# photon.net
KiCad netlist of a schematic drawn in EAGLE
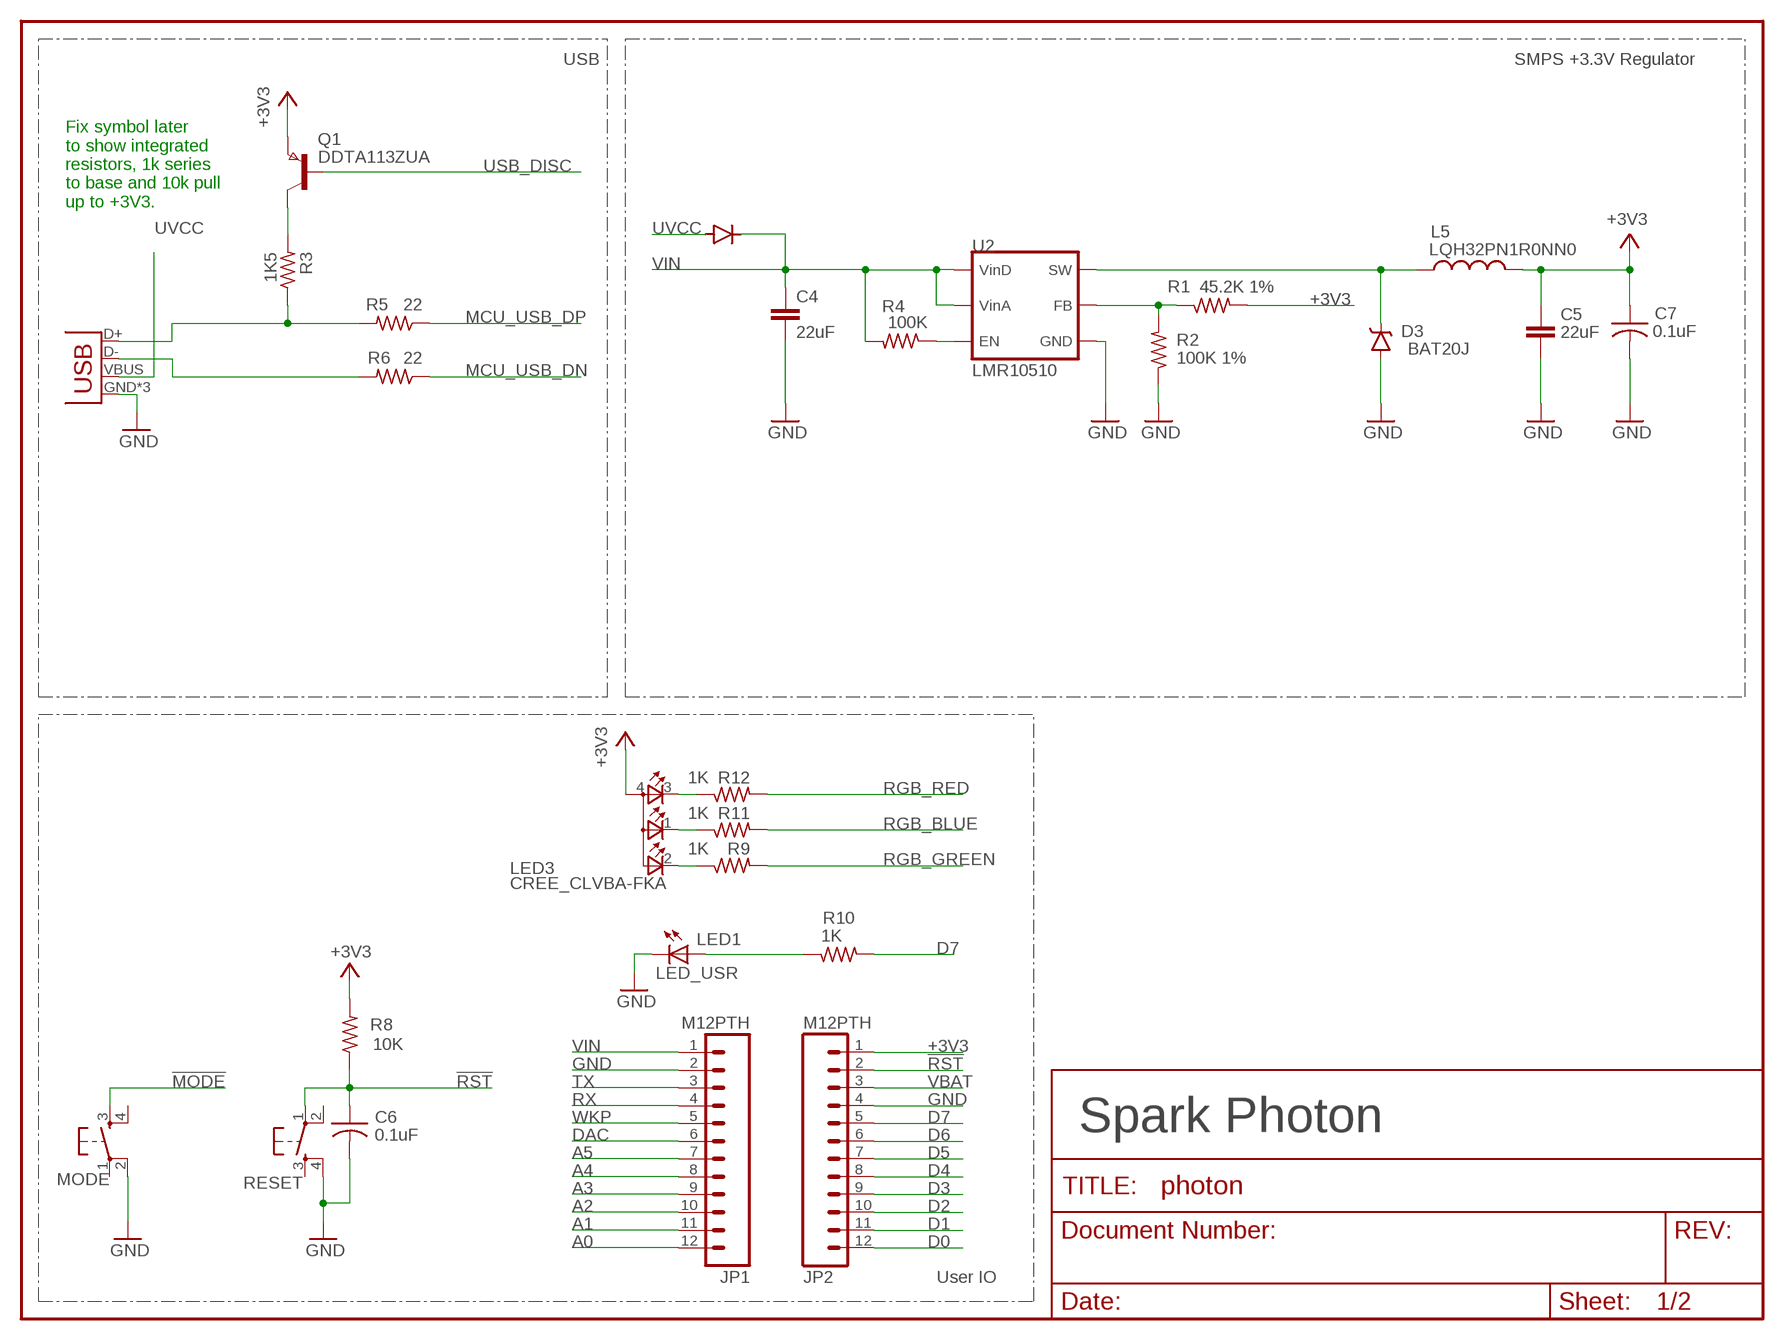
[diagram p0: schematic, sheet 1]
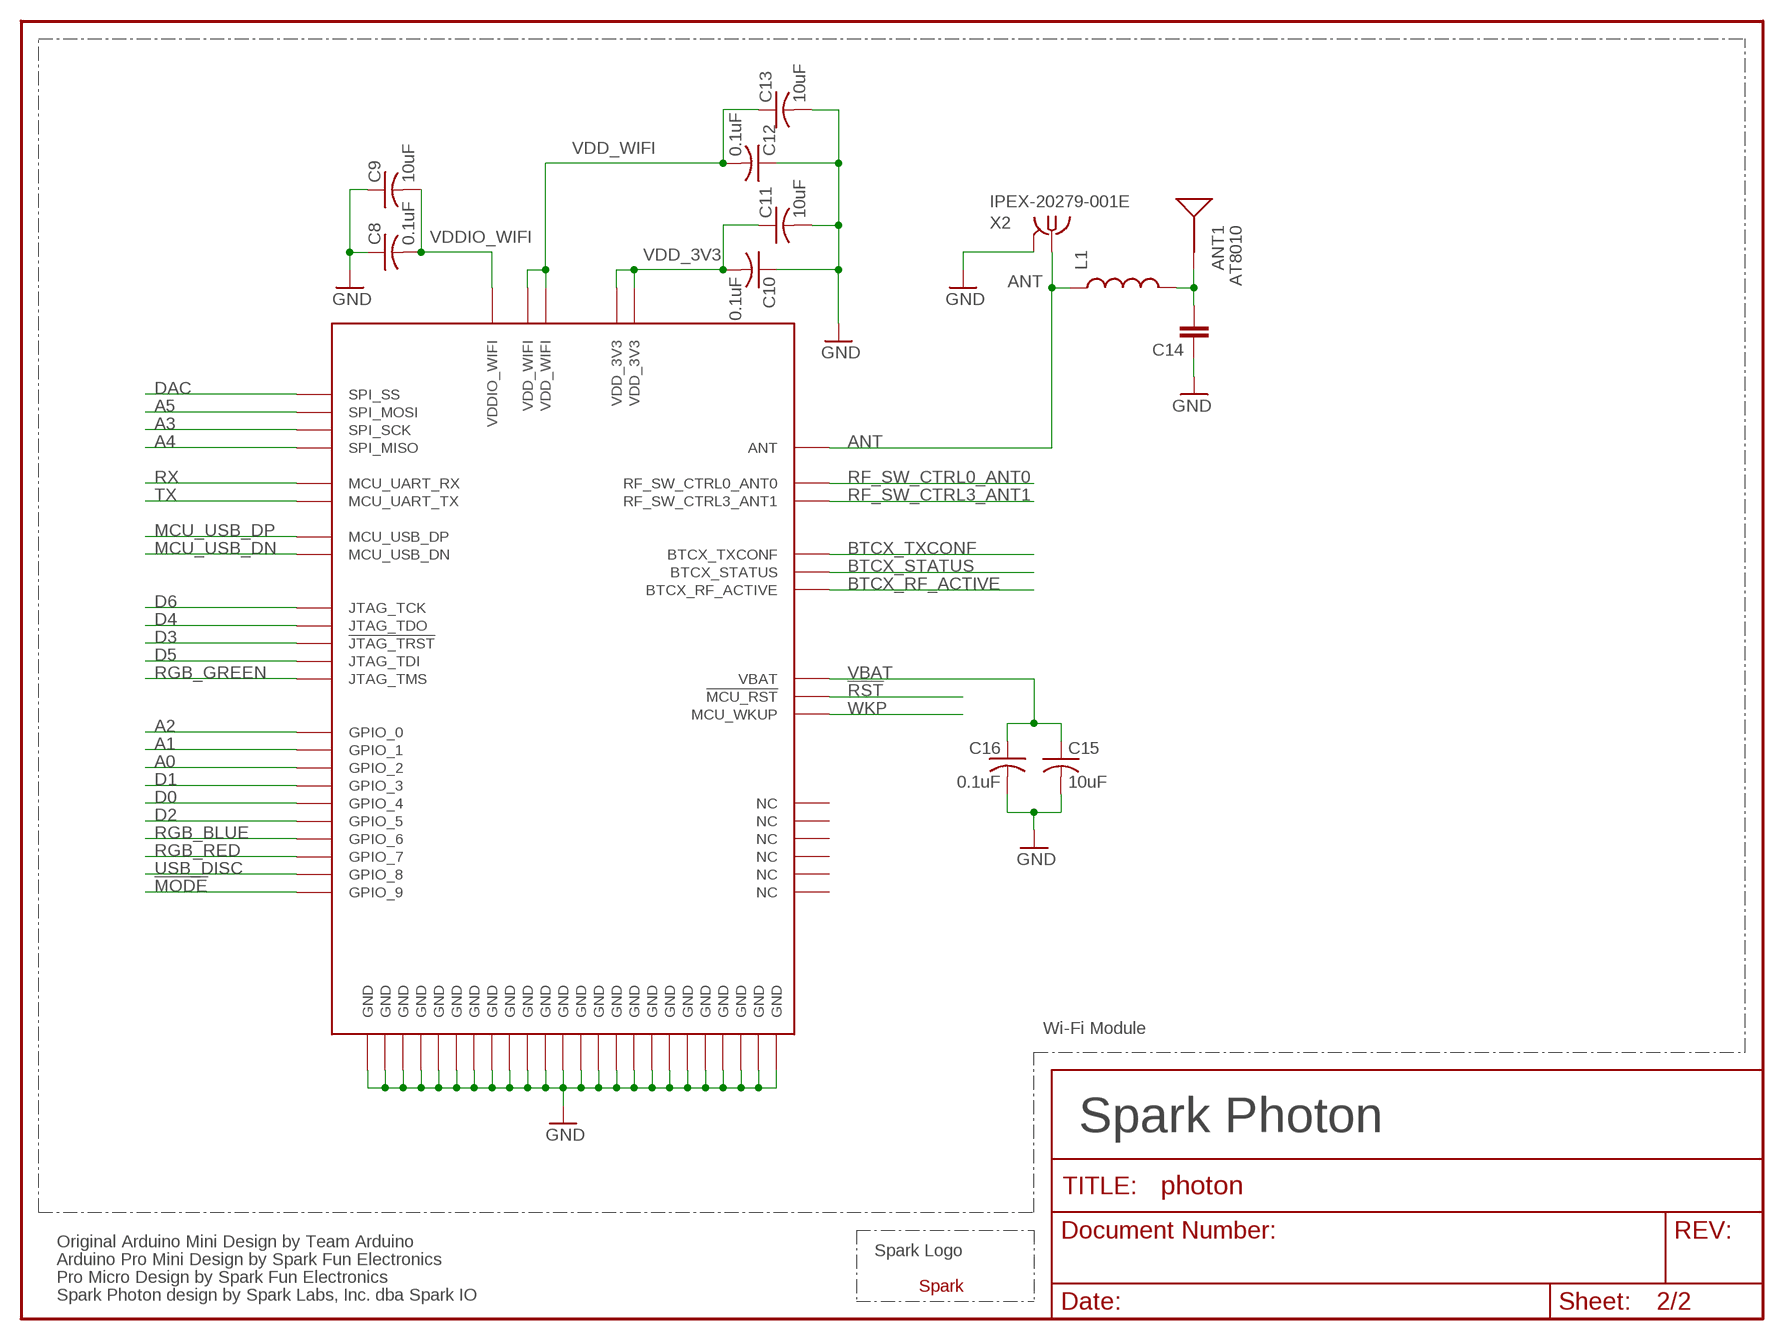
[diagram p1: schematic, sheet 2]

(export (version "E")
  (design (tool "Eeschema 10.0.6"))
  (components
    (comp (ref "ANT1")
      (value "AT8010")
      (footprint "eagle-import:AT8010")
      (libsource (lib "eagle-import") (part "AT8010"))
    )
    (comp (ref "C8")
      (value "0.1uF")
      (footprint "eagle-import:C0402")
      (libsource (lib "eagle-import") (part "C-USC0402"))
    )
    (comp (ref "C9")
      (value "10uF")
      (footprint "eagle-import:C0402")
      (libsource (lib "eagle-import") (part "C-USC0402"))
    )
    (comp (ref "C10")
      (value "0.1uF")
      (footprint "eagle-import:C0402")
      (libsource (lib "eagle-import") (part "C-USC0402"))
    )
    (comp (ref "C11")
      (value "10uF")
      (footprint "eagle-import:C0402")
      (libsource (lib "eagle-import") (part "C-USC0402"))
    )
    (comp (ref "C12")
      (value "0.1uF")
      (footprint "eagle-import:C0402")
      (libsource (lib "eagle-import") (part "C-USC0402"))
    )
    (comp (ref "C13")
      (value "10uF")
      (footprint "eagle-import:C0402")
      (libsource (lib "eagle-import") (part "C-USC0402"))
    )
    (comp (ref "C14")
      (value "CAP0603-CAP")
      (footprint "eagle-import:0603-CAP")
      (libsource (lib "eagle-import") (part "CAP0603-CAP"))
    )
    (comp (ref "C15")
      (value "10uF")
      (footprint "eagle-import:C0402")
      (libsource (lib "eagle-import") (part "C-USC0402"))
    )
    (comp (ref "C16")
      (value "0.1uF")
      (footprint "eagle-import:C0402")
      (libsource (lib "eagle-import") (part "C-USC0402"))
    )
    (comp (ref "L1")
      (value "INDUCTOR-SPARKFUN0603")
      (footprint "eagle-import:0603")
      (libsource (lib "eagle-import") (part "INDUCTOR-SPARKFUN0603"))
    )
    (comp (ref "U$2")
      (value "SPARK_LOGO2")
      (footprint "eagle-import:SPARK_LOGO2")
      (libsource (lib "eagle-import") (part "SPARK_LOGO2"))
    )
    (comp (ref "U1")
      (value "WM-N-BM-09")
      (footprint "eagle-import:WM-N-BM-09")
      (libsource (lib "eagle-import") (part "WM-N-BM-09"))
    )
    (comp (ref "X2")
      (value "IPEX-20279-001E")
      (footprint "eagle-import:IPEX-20279-001E")
      (libsource (lib "eagle-import") (part "IPEX-20279-001E"))
    )
    (comp (ref "C4")
      (value "22uF")
      (footprint "eagle-import:C0603")
      (libsource (lib "eagle-import") (part "C-EUC0603"))
    )
    (comp (ref "C5")
      (value "22uF")
      (footprint "eagle-import:C0603")
      (libsource (lib "eagle-import") (part "C-EUC0603"))
    )
    (comp (ref "C6")
      (value "0.1uF")
      (footprint "eagle-import:C0402")
      (libsource (lib "eagle-import") (part "C-USC0402"))
    )
    (comp (ref "C7")
      (value "0.1uF")
      (footprint "eagle-import:C0402")
      (libsource (lib "eagle-import") (part "C-USC0402"))
    )
    (comp (ref "D1")
      (value "DIODE")
      (footprint "eagle-import:DIODE-DO-220AA(SMP)")
      (libsource (lib "eagle-import") (part "DIODE"))
    )
    (comp (ref "D3")
      (value "BAT20J")
      (footprint "eagle-import:SOD-323")
      (libsource (lib "eagle-import") (part "DIODE-SCHOTTKY-BAT20J"))
    )
    (comp (ref "JP1")
      (value "M12PTH")
      (footprint "eagle-import:1X12-SMALL-PADS")
      (libsource (lib "eagle-import") (part "M12PTH"))
    )
    (comp (ref "JP2")
      (value "M12PTH")
      (footprint "eagle-import:1X12-SMALL-PADS")
      (libsource (lib "eagle-import") (part "M12PTH"))
    )
    (comp (ref "L5")
      (value "LQH32PN1R0NN0")
      (footprint "eagle-import:1210")
      (libsource (lib "eagle-import") (part "INDUCTOR-SPARKFUN1210"))
    )
    (comp (ref "LED3")
      (value "CREE_CLVBA-FKA")
      (footprint "eagle-import:P-LCC-4-3")
      (libsource (lib "eagle-import") (part "TOPLED-3CREE_CLVBA-FKA"))
    )
    (comp (ref "LED_USR")
      (value "LED0603")
      (footprint "eagle-import:LED-0603")
      (libsource (lib "eagle-import") (part "LED0603"))
    )
    (comp (ref "MODE")
      (value "KMR211GLFS")
      (footprint "eagle-import:TACTILE_SWITCH_SMD")
      (libsource (lib "eagle-import") (part "TAC_SWITCHSMD"))
    )
    (comp (ref "Q1")
      (value "DDTA113ZUA")
      (footprint "eagle-import:SOT323")
      (fields (field (name "MPN") "2DB1689-7"))
      (libsource (lib "eagle-import") (part "PNPSOT323"))
    )
    (comp (ref "R1")
      (value "45.2K 1%")
      (footprint "eagle-import:R0402")
      (libsource (lib "eagle-import") (part "R-US_R0402"))
    )
    (comp (ref "R2")
      (value "100K 1%")
      (footprint "eagle-import:R0402")
      (libsource (lib "eagle-import") (part "R-US_R0402"))
    )
    (comp (ref "R3")
      (value "1K5")
      (footprint "eagle-import:R0402")
      (libsource (lib "eagle-import") (part "rcl_R-US_R0402"))
    )
    (comp (ref "R4")
      (value "100K")
      (footprint "eagle-import:R0402")
      (libsource (lib "eagle-import") (part "R-US_R0402"))
    )
    (comp (ref "R5")
      (value "22")
      (footprint "eagle-import:R0402")
      (libsource (lib "eagle-import") (part "rcl_R-US_R0402"))
    )
    (comp (ref "R6")
      (value "22")
      (footprint "eagle-import:R0402")
      (libsource (lib "eagle-import") (part "rcl_R-US_R0402"))
    )
    (comp (ref "R8")
      (value "10K")
      (footprint "eagle-import:R0402")
      (libsource (lib "eagle-import") (part "R-US_R0402"))
    )
    (comp (ref "R9")
      (value "1K")
      (footprint "eagle-import:R0402")
      (libsource (lib "eagle-import") (part "R-US_R0402"))
    )
    (comp (ref "R10")
      (value "1K")
      (footprint "eagle-import:R0402")
      (libsource (lib "eagle-import") (part "R-US_R0402"))
    )
    (comp (ref "R11")
      (value "1K")
      (footprint "eagle-import:R0402")
      (libsource (lib "eagle-import") (part "R-US_R0402"))
    )
    (comp (ref "R12")
      (value "1K")
      (footprint "eagle-import:R0402")
      (libsource (lib "eagle-import") (part "R-US_R0402"))
    )
    (comp (ref "RESET")
      (value "KMR211GLFS")
      (footprint "eagle-import:TACTILE_SWITCH_SMD")
      (libsource (lib "eagle-import") (part "TAC_SWITCHSMD"))
    )
    (comp (ref "U2")
      (value "LMR10510")
      (footprint "eagle-import:WSON-6-PAD")
      (libsource (lib "eagle-import") (part "LMR10510"))
    )
    (comp (ref "X1")
      (value "USB-MICROB")
      (footprint "eagle-import:USB-MICROB-SLOT-HOLE")
      (libsource (lib "eagle-import") (part "USBUSB-MICROB-SLOT-HOLE"))
    )
  )
  (nets
    (net (code "1") (name "+3V3") (class "Default")
      (node (ref "C5") (pin "1") (pinfunction "1_1") (pintype "passive"))
      (node (ref "C7") (pin "1") (pinfunction "1_1") (pintype "passive"))
      (node (ref "JP2") (pin "1") (pinfunction "1_1") (pintype "passive"))
      (node (ref "L5") (pin "2") (pinfunction "2_2") (pintype "passive"))
      (node (ref "LED3") (pin "4") (pinfunction "A2_4") (pintype "passive"))
      (node (ref "Q1") (pin "3") (pinfunction "E_3") (pintype "passive"))
      (node (ref "R1") (pin "2") (pinfunction "2_2") (pintype "passive"))
      (node (ref "R8") (pin "2") (pinfunction "2_2") (pintype "passive"))
    )
    (net (code "2") (name "A0") (class "Default")
      (node (ref "JP1") (pin "12") (pinfunction "12_12") (pintype "passive"))
      (node (ref "U1") (pin "P$6") (pinfunction "GPIO_2_P$6") (pintype "bidirectional"))
    )
    (net (code "3") (name "A1") (class "Default")
      (node (ref "JP1") (pin "11") (pinfunction "11_11") (pintype "passive"))
      (node (ref "U1") (pin "P$7") (pinfunction "GPIO_1_P$7") (pintype "bidirectional"))
    )
    (net (code "4") (name "A2") (class "Default")
      (node (ref "JP1") (pin "10") (pinfunction "10_10") (pintype "passive"))
      (node (ref "U1") (pin "P$8") (pinfunction "GPIO_0_P$8") (pintype "bidirectional"))
    )
    (net (code "5") (name "A3") (class "Default")
      (node (ref "JP1") (pin "9") (pinfunction "9_9") (pintype "passive"))
      (node (ref "U1") (pin "P$24") (pinfunction "SPI_SCK_P$24") (pintype "bidirectional"))
    )
    (net (code "6") (name "A4") (class "Default")
      (node (ref "JP1") (pin "8") (pinfunction "8_8") (pintype "passive"))
      (node (ref "U1") (pin "P$25") (pinfunction "SPI_MISO_P$25") (pintype "bidirectional"))
    )
    (net (code "7") (name "A5") (class "Default")
      (node (ref "JP1") (pin "7") (pinfunction "7_7") (pintype "passive"))
      (node (ref "U1") (pin "P$23") (pinfunction "SPI_MOSI_P$23") (pintype "bidirectional"))
    )
    (net (code "8") (name "ANT") (class "Default")
      (node (ref "L1") (pin "1") (pinfunction "1_1") (pintype "passive"))
      (node (ref "U1") (pin "P$15") (pinfunction "ANT_P$15") (pintype "bidirectional"))
      (node (ref "X2") (pin "1") (pinfunction "1_1") (pintype "passive"))
    )
    (net (code "9") (name "BTCX_RF_ACTIVE") (class "Default")
      (node (ref "U1") (pin "P$9") (pinfunction "BTCX_RF_ACTIVE_P$9") (pintype "bidirectional"))
    )
    (net (code "10") (name "BTCX_STATUS") (class "Default")
      (node (ref "U1") (pin "P$10") (pinfunction "BTCX_STATUS_P$10") (pintype "bidirectional"))
    )
    (net (code "11") (name "BTCX_TXCONF") (class "Default")
      (node (ref "U1") (pin "P$11") (pinfunction "BTCX_TXCONF_P$11") (pintype "bidirectional"))
    )
    (net (code "12") (name "D0") (class "Default")
      (node (ref "JP2") (pin "12") (pinfunction "12_12") (pintype "passive"))
      (node (ref "U1") (pin "P$4") (pinfunction "GPIO_4_P$4") (pintype "bidirectional"))
    )
    (net (code "13") (name "D1") (class "Default")
      (node (ref "JP2") (pin "11") (pinfunction "11_11") (pintype "passive"))
      (node (ref "U1") (pin "P$5") (pinfunction "GPIO_3_P$5") (pintype "bidirectional"))
    )
    (net (code "14") (name "D2") (class "Default")
      (node (ref "JP2") (pin "10") (pinfunction "10_10") (pintype "passive"))
      (node (ref "U1") (pin "P$3") (pinfunction "GPIO_5_P$3") (pintype "bidirectional"))
    )
    (net (code "15") (name "D3") (class "Default")
      (node (ref "JP2") (pin "9") (pinfunction "9_9") (pintype "passive"))
      (node (ref "U1") (pin "P$42") (pinfunction "~{JTAG_TRST}_P$42") (pintype "bidirectional"))
    )
    (net (code "16") (name "D4") (class "Default")
      (node (ref "JP2") (pin "8") (pinfunction "8_8") (pintype "passive"))
      (node (ref "U1") (pin "P$41") (pinfunction "JTAG_TDO_P$41") (pintype "bidirectional"))
    )
    (net (code "17") (name "D5") (class "Default")
      (node (ref "JP2") (pin "7") (pinfunction "7_7") (pintype "passive"))
      (node (ref "U1") (pin "P$43") (pinfunction "JTAG_TDI_P$43") (pintype "bidirectional"))
    )
    (net (code "18") (name "D6") (class "Default")
      (node (ref "JP2") (pin "6") (pinfunction "6_6") (pintype "passive"))
      (node (ref "U1") (pin "P$40") (pinfunction "JTAG_TCK_P$40") (pintype "bidirectional"))
    )
    (net (code "19") (name "D7") (class "Default")
      (node (ref "JP2") (pin "5") (pinfunction "5_5") (pintype "passive"))
      (node (ref "R10") (pin "2") (pinfunction "2_2") (pintype "passive"))
    )
    (net (code "20") (name "DAC") (class "Default")
      (node (ref "JP1") (pin "6") (pinfunction "6_6") (pintype "passive"))
      (node (ref "U1") (pin "P$22") (pinfunction "SPI_SS_P$22") (pintype "bidirectional"))
    )
    (net (code "21") (name "GND") (class "Default")
      (node (ref "C10") (pin "1") (pinfunction "1_1") (pintype "passive"))
      (node (ref "C11") (pin "2") (pinfunction "2_2") (pintype "passive"))
      (node (ref "C12") (pin "1") (pinfunction "1_1") (pintype "passive"))
      (node (ref "C13") (pin "2") (pinfunction "2_2") (pintype "passive"))
      (node (ref "C14") (pin "1") (pinfunction "1_1") (pintype "passive"))
      (node (ref "C15") (pin "2") (pinfunction "2_2") (pintype "passive"))
      (node (ref "C16") (pin "2") (pinfunction "2_2") (pintype "passive"))
      (node (ref "C4") (pin "2") (pinfunction "2_2") (pintype "passive"))
      (node (ref "C5") (pin "2") (pinfunction "2_2") (pintype "passive"))
      (node (ref "C6") (pin "2") (pinfunction "2_2") (pintype "passive"))
      (node (ref "C7") (pin "2") (pinfunction "2_2") (pintype "passive"))
      (node (ref "C8") (pin "1") (pinfunction "1_1") (pintype "passive"))
      (node (ref "C9") (pin "1") (pinfunction "1_1") (pintype "passive"))
      (node (ref "D3") (pin "A") (pinfunction "A_A") (pintype "passive"))
      (node (ref "JP1") (pin "2") (pinfunction "2_2") (pintype "passive"))
      (node (ref "JP2") (pin "4") (pinfunction "4_4") (pintype "passive"))
      (node (ref "LED_USR") (pin "C") (pinfunction "C_C") (pintype "passive"))
      (node (ref "MODE") (pin "2") (pinfunction "2_2") (pintype "passive"))
      (node (ref "R2") (pin "1") (pinfunction "1_1") (pintype "passive"))
      (node (ref "RESET") (pin "4") (pinfunction "4_4") (pintype "passive"))
      (node (ref "U1") (pin "P$14") (pinfunction "GND_P$14") (pintype "bidirectional"))
      (node (ref "U1") (pin "P$16") (pinfunction "GND_P$16") (pintype "bidirectional"))
      (node (ref "U1") (pin "P$17") (pinfunction "GND_P$17") (pintype "bidirectional"))
      (node (ref "U1") (pin "P$18") (pinfunction "GND_P$18") (pintype "bidirectional"))
      (node (ref "U1") (pin "P$21") (pinfunction "GND_P$21") (pintype "bidirectional"))
      (node (ref "U1") (pin "P$29") (pinfunction "GND_P$29") (pintype "bidirectional"))
      (node (ref "U1") (pin "P$30") (pinfunction "GND_P$30") (pintype "bidirectional"))
      (node (ref "U1") (pin "P$37") (pinfunction "GND_P$37") (pintype "bidirectional"))
      (node (ref "U1") (pin "P$45") (pinfunction "GND_P$45") (pintype "bidirectional"))
      (node (ref "U1") (pin "P$48") (pinfunction "GND_P$48") (pintype "bidirectional"))
      (node (ref "U1") (pin "P$50") (pinfunction "GND_P$50") (pintype "bidirectional"))
      (node (ref "U1") (pin "P$55") (pinfunction "GND_P$55") (pintype "bidirectional"))
      (node (ref "U1") (pin "P$56") (pinfunction "GND_P$56") (pintype "bidirectional"))
      (node (ref "U1") (pin "P$57") (pinfunction "GND_P$57") (pintype "bidirectional"))
      (node (ref "U1") (pin "P$58") (pinfunction "GND_P$58") (pintype "bidirectional"))
      (node (ref "U1") (pin "P$59") (pinfunction "GND_P$59") (pintype "bidirectional"))
      (node (ref "U1") (pin "P$60") (pinfunction "GND_P$60") (pintype "bidirectional"))
      (node (ref "U1") (pin "P$61") (pinfunction "GND_P$61") (pintype "bidirectional"))
      (node (ref "U1") (pin "P$62") (pinfunction "GND_P$62") (pintype "bidirectional"))
      (node (ref "U1") (pin "P$63") (pinfunction "GND_P$63") (pintype "bidirectional"))
      (node (ref "U1") (pin "P$64") (pinfunction "GND_P$64") (pintype "bidirectional"))
      (node (ref "U1") (pin "P$65") (pinfunction "GND_P$65") (pintype "bidirectional"))
      (node (ref "U1") (pin "P$66") (pinfunction "GND_P$66") (pintype "bidirectional"))
      (node (ref "U1") (pin "P$67") (pinfunction "GND_P$67") (pintype "bidirectional"))
      (node (ref "U2") (pin "2") (pinfunction "GND_2") (pintype "power_in"))
      (node (ref "U2") (pin "PAD") (pinfunction "GND_PAD") (pintype "power_in"))
      (node (ref "X1") (pin "GND") (pinfunction "GND_GND") (pintype "bidirectional"))
      (node (ref "X1") (pin "MT1") (pinfunction "GND_MT1") (pintype "bidirectional"))
      (node (ref "X1") (pin "MT2") (pinfunction "GND_MT2") (pintype "bidirectional"))
      (node (ref "X2") (pin "2@1") (pinfunction "GND_2@1") (pintype "passive"))
      (node (ref "X2") (pin "2@2") (pinfunction "GND_2@2") (pintype "passive"))
    )
    (net (code "22") (name "LED1") (class "Default")
      (node (ref "LED_USR") (pin "A") (pinfunction "A_A") (pintype "passive"))
      (node (ref "R10") (pin "1") (pinfunction "1_1") (pintype "passive"))
    )
    (net (code "23") (name "MCU_USB_DN") (class "Default")
      (node (ref "R6") (pin "1") (pinfunction "1_1") (pintype "passive"))
      (node (ref "U1") (pin "P$52") (pinfunction "MCU_USB_DN_P$52") (pintype "bidirectional"))
    )
    (net (code "24") (name "MCU_USB_DP") (class "Default")
      (node (ref "R5") (pin "1") (pinfunction "1_1") (pintype "passive"))
      (node (ref "U1") (pin "P$51") (pinfunction "MCU_USB_DP_P$51") (pintype "bidirectional"))
    )
    (net (code "25") (name "Net-(ANT1-SIGNAL)") (class "Default")
      (node (ref "ANT1") (pin "SIG") (pinfunction "SIGNAL_SIG") (pintype "bidirectional"))
      (node (ref "C14") (pin "2") (pinfunction "2_2") (pintype "passive"))
      (node (ref "L1") (pin "2") (pinfunction "2_2") (pintype "passive"))
    )
    (net (code "26") (name "Net-(LED3-CBLUE)") (class "Default")
      (node (ref "LED3") (pin "1") (pinfunction "CBLUE_1") (pintype "passive"))
      (node (ref "R11") (pin "1") (pinfunction "1_1") (pintype "passive"))
    )
    (net (code "27") (name "Net-(LED3-CGREEN)") (class "Default")
      (node (ref "LED3") (pin "2") (pinfunction "CGREEN_2") (pintype "passive"))
      (node (ref "R9") (pin "1") (pinfunction "1_1") (pintype "passive"))
    )
    (net (code "28") (name "Net-(LED3-CRED)") (class "Default")
      (node (ref "LED3") (pin "3") (pinfunction "CRED_3") (pintype "passive"))
      (node (ref "R12") (pin "1") (pinfunction "1_1") (pintype "passive"))
    )
    (net (code "29") (name "Net-(Q1-C)") (class "Default")
      (node (ref "Q1") (pin "1") (pinfunction "C_1") (pintype "passive"))
      (node (ref "R3") (pin "2") (pinfunction "2_2") (pintype "passive"))
    )
    (net (code "30") (name "Net-(R3-Pad1)") (class "Default")
      (node (ref "R3") (pin "1") (pinfunction "1_1") (pintype "passive"))
      (node (ref "R5") (pin "2") (pinfunction "2_2") (pintype "passive"))
      (node (ref "X1") (pin "D+") (pinfunction "D+_D+") (pintype "bidirectional"))
    )
    (net (code "31") (name "Net-(R6-Pad2)") (class "Default")
      (node (ref "R6") (pin "2") (pinfunction "2_2") (pintype "passive"))
      (node (ref "X1") (pin "D-") (pinfunction "D-_D-") (pintype "bidirectional"))
    )
    (net (code "32") (name "Net-(U2-EN)") (class "Default")
      (node (ref "R4") (pin "1") (pinfunction "1_1") (pintype "passive"))
      (node (ref "U2") (pin "6") (pinfunction "EN_6") (pintype "input"))
    )
    (net (code "33") (name "Net-(U2-FB)") (class "Default")
      (node (ref "R1") (pin "1") (pinfunction "1_1") (pintype "passive"))
      (node (ref "R2") (pin "2") (pinfunction "2_2") (pintype "passive"))
      (node (ref "U2") (pin "1") (pinfunction "FB_1") (pintype "input"))
    )
    (net (code "34") (name "Net-(U2-SW)") (class "Default")
      (node (ref "D3") (pin "C") (pinfunction "C_C") (pintype "passive"))
      (node (ref "L5") (pin "1") (pinfunction "1_1") (pintype "passive"))
      (node (ref "U2") (pin "3") (pinfunction "SW_3") (pintype "output"))
    )
    (net (code "35") (name "RF_SW_CTRL0_ANT0") (class "Default")
      (node (ref "U1") (pin "P$13") (pinfunction "RF_SW_CTRL0_ANT0_P$13") (pintype "bidirectional"))
    )
    (net (code "36") (name "RF_SW_CTRL3_ANT1") (class "Default")
      (node (ref "U1") (pin "P$12") (pinfunction "RF_SW_CTRL3_ANT1_P$12") (pintype "bidirectional"))
    )
    (net (code "37") (name "RGB_BLUE") (class "Default")
      (node (ref "R11") (pin "2") (pinfunction "2_2") (pintype "passive"))
      (node (ref "U1") (pin "P$2") (pinfunction "GPIO_6_P$2") (pintype "bidirectional"))
    )
    (net (code "38") (name "RGB_GREEN") (class "Default")
      (node (ref "R9") (pin "2") (pinfunction "2_2") (pintype "passive"))
      (node (ref "U1") (pin "P$44") (pinfunction "JTAG_TMS_P$44") (pintype "bidirectional"))
    )
    (net (code "39") (name "RGB_RED") (class "Default")
      (node (ref "R12") (pin "2") (pinfunction "2_2") (pintype "passive"))
      (node (ref "U1") (pin "P$1") (pinfunction "GPIO_7_P$1") (pintype "bidirectional"))
    )
    (net (code "40") (name "RX") (class "Default")
      (node (ref "JP1") (pin "4") (pinfunction "4_4") (pintype "passive"))
      (node (ref "U1") (pin "P$38") (pinfunction "MCU_UART_RX_P$38") (pintype "bidirectional"))
    )
    (net (code "41") (name "TX") (class "Default")
      (node (ref "JP1") (pin "3") (pinfunction "3_3") (pintype "passive"))
      (node (ref "U1") (pin "P$39") (pinfunction "MCU_UART_TX_P$39") (pintype "bidirectional"))
    )
    (net (code "42") (name "USB_DISC") (class "Default")
      (node (ref "Q1") (pin "2") (pinfunction "B_2") (pintype "passive"))
      (node (ref "U1") (pin "P$54") (pinfunction "GPIO_8_P$54") (pintype "bidirectional"))
    )
    (net (code "43") (name "UVCC") (class "Default")
      (node (ref "D1") (pin "ANODE") (pinfunction "ANODE_ANODE") (pintype "bidirectional"))
      (node (ref "X1") (pin "VBUS") (pinfunction "VBUS_VBUS") (pintype "bidirectional"))
    )
    (net (code "44") (name "VBAT") (class "Default")
      (node (ref "C15") (pin "1") (pinfunction "1_1") (pintype "passive"))
      (node (ref "C16") (pin "1") (pinfunction "1_1") (pintype "passive"))
      (node (ref "JP2") (pin "3") (pinfunction "3_3") (pintype "passive"))
      (node (ref "U1") (pin "P$28") (pinfunction "VBAT_P$28") (pintype "bidirectional"))
    )
    (net (code "45") (name "VDDIO_WIFI") (class "Default")
      (node (ref "C8") (pin "2") (pinfunction "2_2") (pintype "passive"))
      (node (ref "C9") (pin "2") (pinfunction "2_2") (pintype "passive"))
      (node (ref "U1") (pin "P$49") (pinfunction "VDDIO_WIFI_P$49") (pintype "bidirectional"))
    )
    (net (code "46") (name "VDD_3V3") (class "Default")
      (node (ref "C10") (pin "2") (pinfunction "2_2") (pintype "passive"))
      (node (ref "C11") (pin "1") (pinfunction "1_1") (pintype "passive"))
      (node (ref "U1") (pin "P$46") (pinfunction "VDD_3V3_P$46") (pintype "bidirectional"))
      (node (ref "U1") (pin "P$47") (pinfunction "VDD_3V3_P$47") (pintype "bidirectional"))
    )
    (net (code "47") (name "VDD_WIFI") (class "Default")
      (node (ref "C12") (pin "2") (pinfunction "2_2") (pintype "passive"))
      (node (ref "C13") (pin "1") (pinfunction "1_1") (pintype "passive"))
      (node (ref "U1") (pin "P$19") (pinfunction "VDD_WIFI_P$19") (pintype "bidirectional"))
      (node (ref "U1") (pin "P$20") (pinfunction "VDD_WIFI_P$20") (pintype "bidirectional"))
    )
    (net (code "48") (name "VIN") (class "Default")
      (node (ref "C4") (pin "1") (pinfunction "1_1") (pintype "passive"))
      (node (ref "D1") (pin "CATHODE") (pinfunction "CATHODE_CATHODE") (pintype "bidirectional"))
      (node (ref "JP1") (pin "1") (pinfunction "1_1") (pintype "passive"))
      (node (ref "R4") (pin "2") (pinfunction "2_2") (pintype "passive"))
      (node (ref "U2") (pin "4") (pinfunction "VIND_4") (pintype "input"))
      (node (ref "U2") (pin "5") (pinfunction "VINA_5") (pintype "input"))
    )
    (net (code "49") (name "WKP") (class "Default")
      (node (ref "JP1") (pin "5") (pinfunction "5_5") (pintype "passive"))
      (node (ref "U1") (pin "P$27") (pinfunction "MCU_WKUP_P$27") (pintype "bidirectional"))
    )
    (net (code "50") (name "unconnected-(MODE-Pad1)") (class "Default")
      (node (ref "MODE") (pin "1") (pinfunction "1_1") (pintype "passive"))
    )
    (net (code "51") (name "unconnected-(MODE-Pad4)") (class "Default")
      (node (ref "MODE") (pin "4") (pinfunction "4_4") (pintype "passive"))
    )
    (net (code "52") (name "unconnected-(RESET-Pad2)") (class "Default")
      (node (ref "RESET") (pin "2") (pinfunction "2_2") (pintype "passive"))
    )
    (net (code "53") (name "unconnected-(RESET-Pad3)") (class "Default")
      (node (ref "RESET") (pin "3") (pinfunction "3_3") (pintype "passive"))
    )
    (net (code "54") (name "unconnected-(U1-NC-PadP$31)") (class "Default")
      (node (ref "U1") (pin "P$31") (pinfunction "NC_P$31") (pintype "bidirectional"))
    )
    (net (code "55") (name "unconnected-(U1-NC-PadP$32)") (class "Default")
      (node (ref "U1") (pin "P$32") (pinfunction "NC_P$32") (pintype "bidirectional"))
    )
    (net (code "56") (name "unconnected-(U1-NC-PadP$33)") (class "Default")
      (node (ref "U1") (pin "P$33") (pinfunction "NC_P$33") (pintype "bidirectional"))
    )
    (net (code "57") (name "unconnected-(U1-NC-PadP$34)") (class "Default")
      (node (ref "U1") (pin "P$34") (pinfunction "NC_P$34") (pintype "bidirectional"))
    )
    (net (code "58") (name "unconnected-(U1-NC-PadP$35)") (class "Default")
      (node (ref "U1") (pin "P$35") (pinfunction "NC_P$35") (pintype "bidirectional"))
    )
    (net (code "59") (name "unconnected-(U1-NC-PadP$36)") (class "Default")
      (node (ref "U1") (pin "P$36") (pinfunction "NC_P$36") (pintype "bidirectional"))
    )
    (net (code "60") (name "~{MODE}") (class "Default")
      (node (ref "MODE") (pin "3") (pinfunction "3_3") (pintype "passive"))
      (node (ref "U1") (pin "P$53") (pinfunction "GPIO_9_P$53") (pintype "bidirectional"))
    )
    (net (code "61") (name "~{RST}") (class "Default")
      (node (ref "C6") (pin "1") (pinfunction "1_1") (pintype "passive"))
      (node (ref "JP2") (pin "2") (pinfunction "2_2") (pintype "passive"))
      (node (ref "R8") (pin "1") (pinfunction "1_1") (pintype "passive"))
      (node (ref "RESET") (pin "1") (pinfunction "1_1") (pintype "passive"))
      (node (ref "U1") (pin "P$26") (pinfunction "~{MCU_RST}_P$26") (pintype "bidirectional"))
    )
  )
)
